# SCH.net
KiCad netlist of a schematic drawn in Altium Designer
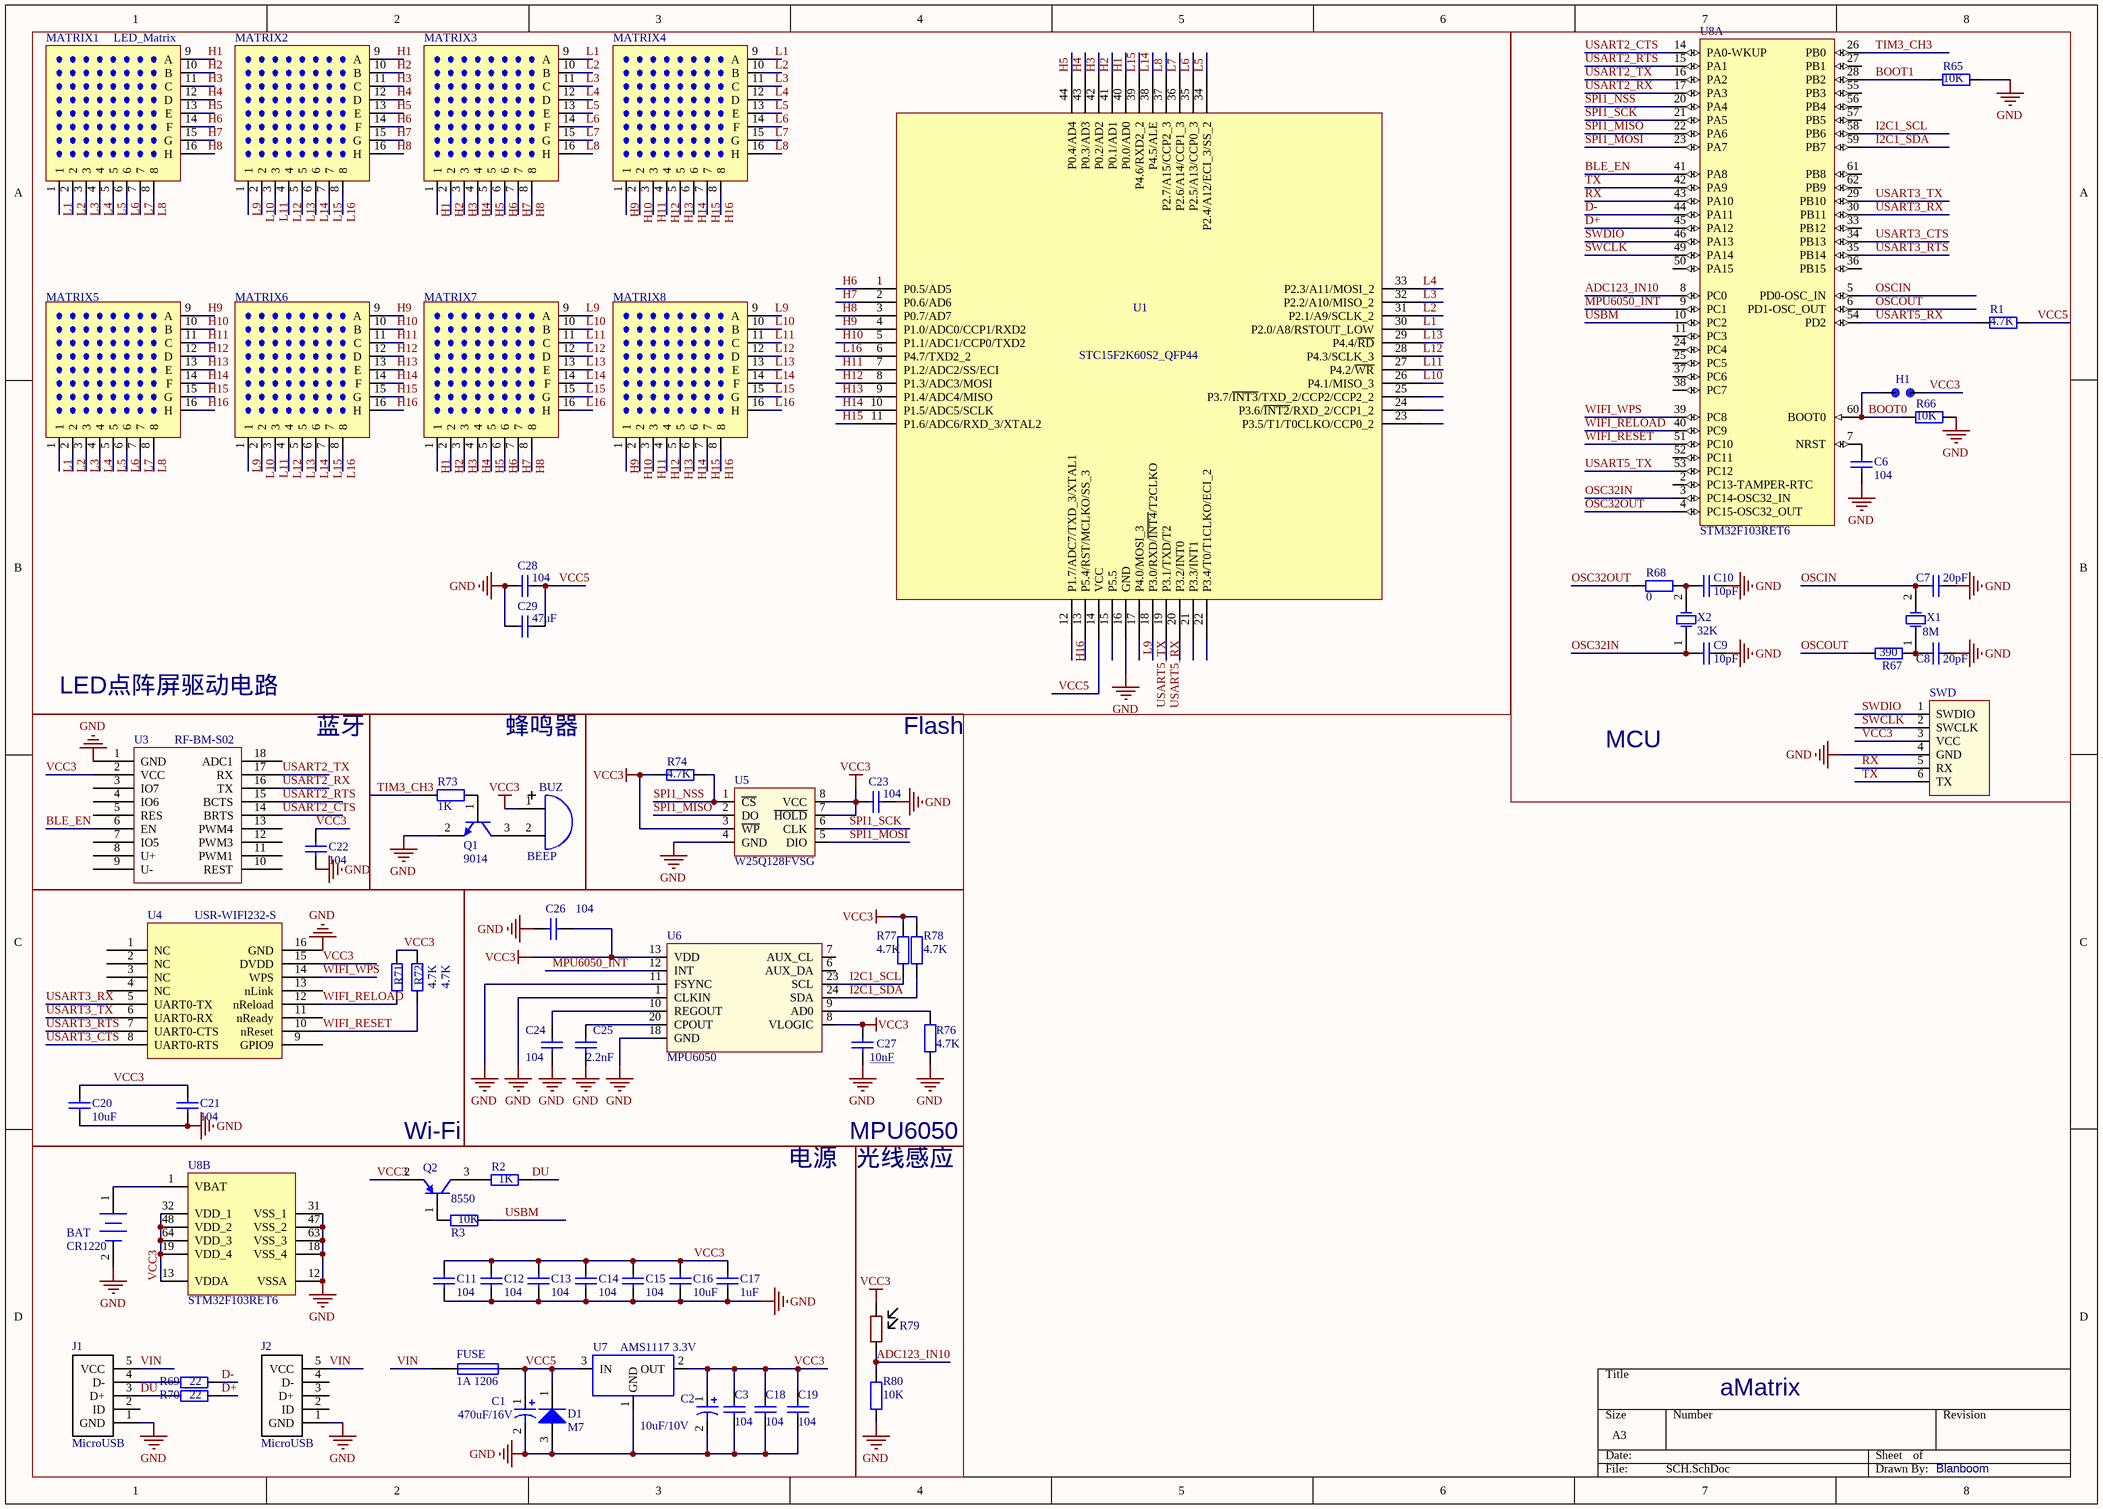
[diagram p0: SCH.SchDoc]

(export (version "E")
  (design (tool "Eeschema 10.0.6"))
  (components
    (comp (ref "BAT")
      (value "CR1220")
      (footprint "CR1220")
      (description "Multicell Battery")
      (libsource (lib "Miscellaneous Devices") (part "Battery"))
    )
    (comp (ref "BUZ") (value "BEEP") (footprint "BEEP") (libsource (lib "MyLib") (part "BEEP")))
    (comp (ref "C1")
      (value "470uF/16V")
      (footprint "7343")
      (description "Polarized Capacitor (Radial)")
      (fields (field (name "Comment") "Cap Pol1"))
      (libsource (lib "Miscellaneous Devices") (part "Cap Pol1"))
    )
    (comp (ref "C2")
      (value "10uF/10V")
      (footprint "1206_Diode")
      (description "Polarized Capacitor (Radial)")
      (fields (field (name "Comment") "Cap Pol1"))
      (libsource (lib "Miscellaneous Devices") (part "Cap Pol1"))
    )
    (comp (ref "C3")
      (value "104")
      (footprint "0805")
      (description "Capacitor")
      (fields (field (name "Comment") "Cap"))
      (libsource (lib "Miscellaneous Devices") (part "Cap"))
    )
    (comp (ref "C6")
      (value "104")
      (footprint "0805")
      (description "Capacitor")
      (libsource (lib "Miscellaneous Devices") (part "Cap"))
    )
    (comp (ref "C7")
      (value "20pF")
      (footprint "0805")
      (description "Capacitor")
      (fields (field (name "Comment") "Cap"))
      (libsource (lib "Miscellaneous Devices") (part "Cap"))
    )
    (comp (ref "C8")
      (value "20pF")
      (footprint "0805")
      (description "Capacitor")
      (fields (field (name "Comment") "Cap"))
      (libsource (lib "Miscellaneous Devices") (part "Cap"))
    )
    (comp (ref "C9")
      (value "10pF")
      (footprint "0805")
      (description "Capacitor")
      (fields (field (name "Comment") "Cap"))
      (libsource (lib "Miscellaneous Devices") (part "Cap"))
    )
    (comp (ref "C10")
      (value "10pF")
      (footprint "0805")
      (description "Capacitor")
      (fields (field (name "Comment") "Cap"))
      (libsource (lib "Miscellaneous Devices") (part "Cap"))
    )
    (comp (ref "C11")
      (value "104")
      (footprint "0805")
      (description "Capacitor")
      (fields (field (name "Comment") "Cap"))
      (libsource (lib "Miscellaneous Devices") (part "Cap"))
    )
    (comp (ref "C12")
      (value "104")
      (footprint "0805")
      (description "Capacitor")
      (fields (field (name "Comment") "Cap"))
      (libsource (lib "Miscellaneous Devices") (part "Cap"))
    )
    (comp (ref "C13")
      (value "104")
      (footprint "0805")
      (description "Capacitor")
      (fields (field (name "Comment") "Cap"))
      (libsource (lib "Miscellaneous Devices") (part "Cap"))
    )
    (comp (ref "C14")
      (value "104")
      (footprint "0805")
      (description "Capacitor")
      (fields (field (name "Comment") "Cap"))
      (libsource (lib "Miscellaneous Devices") (part "Cap"))
    )
    (comp (ref "C15")
      (value "104")
      (footprint "0805")
      (description "Capacitor")
      (fields (field (name "Comment") "Cap"))
      (libsource (lib "Miscellaneous Devices") (part "Cap"))
    )
    (comp (ref "C16")
      (value "10uF")
      (footprint "0805")
      (description "Capacitor")
      (fields (field (name "Comment") "Cap"))
      (libsource (lib "Miscellaneous Devices") (part "Cap"))
    )
    (comp (ref "C17")
      (value "1uF")
      (footprint "0805")
      (description "Capacitor")
      (fields (field (name "Comment") "Cap"))
      (libsource (lib "Miscellaneous Devices") (part "Cap"))
    )
    (comp (ref "C18")
      (value "104")
      (footprint "0805")
      (description "Capacitor")
      (fields (field (name "Comment") "Cap"))
      (libsource (lib "Miscellaneous Devices") (part "Cap"))
    )
    (comp (ref "C19")
      (value "104")
      (footprint "0805")
      (description "Capacitor")
      (fields (field (name "Comment") "Cap"))
      (libsource (lib "Miscellaneous Devices") (part "Cap"))
    )
    (comp (ref "C20")
      (value "10uF")
      (footprint "0805")
      (description "Capacitor")
      (fields (field (name "Comment") "Cap"))
      (libsource (lib "Miscellaneous Devices") (part "Cap"))
    )
    (comp (ref "C21")
      (value "104")
      (footprint "0805")
      (description "Capacitor")
      (fields (field (name "Comment") "Cap"))
      (libsource (lib "Miscellaneous Devices") (part "Cap"))
    )
    (comp (ref "C22")
      (value "104")
      (footprint "0805")
      (description "Capacitor")
      (fields (field (name "Comment") "Cap"))
      (libsource (lib "Miscellaneous Devices") (part "Cap"))
    )
    (comp (ref "C23")
      (value "104")
      (footprint "0805")
      (description "Capacitor")
      (fields (field (name "Comment") "Cap"))
      (libsource (lib "Miscellaneous Devices") (part "Cap"))
    )
    (comp (ref "C24")
      (value "104")
      (footprint "0805")
      (description "Capacitor")
      (fields (field (name "Comment") "Cap"))
      (libsource (lib "Miscellaneous Devices") (part "Cap"))
    )
    (comp (ref "C25")
      (value "2.2nF")
      (footprint "0805")
      (description "Capacitor")
      (fields (field (name "Comment") "Cap"))
      (libsource (lib "Miscellaneous Devices") (part "Cap"))
    )
    (comp (ref "C26")
      (value "104")
      (footprint "0805")
      (description "Capacitor")
      (fields (field (name "Comment") "Cap"))
      (libsource (lib "Miscellaneous Devices") (part "Cap"))
    )
    (comp (ref "C27")
      (value "10nF")
      (footprint "0805")
      (description "Capacitor")
      (fields (field (name "Comment") "Cap"))
      (libsource (lib "Miscellaneous Devices") (part "Cap"))
    )
    (comp (ref "C28")
      (value "104")
      (footprint "0805")
      (description "Capacitor")
      (fields (field (name "Comment") "Cap"))
      (libsource (lib "Miscellaneous Devices") (part "Cap"))
    )
    (comp (ref "C29")
      (value "47uF")
      (footprint "0805")
      (description "Capacitor")
      (fields (field (name "Comment") "Cap"))
      (libsource (lib "Miscellaneous Devices") (part "Cap"))
    )
    (comp (ref "D1")
      (value "M7")
      (footprint "DO-214AC")
      (description "Default Diode")
      (libsource (lib "Miscellaneous Devices") (part "Diode"))
    )
    (comp (ref "FUSE")
      (value "1A 1206")
      (footprint "1206")
      (description "Fuse")
      (libsource (lib "Miscellaneous Devices") (part "Fuse 1"))
    )
    (comp (ref "H1") (value "Header2") (footprint "Header2") (libsource (lib "SCH_Library") (part "Header2")))
    (comp (ref "J1")
      (value "MicroUSB")
      (footprint "MicroUSB")
      (description "Imported")
      (libsource (lib "SCH_Library") (part "MicroUSB"))
    )
    (comp (ref "J2")
      (value "MicroUSB")
      (footprint "MicroUSB")
      (description "Imported")
      (libsource (lib "SCH_Library") (part "MicroUSB"))
    )
    (comp (ref "MATRIX1")
      (value "LED_Matrix")
      (footprint "LED_Matrix")
      (libsource (lib "SCH_Library") (part "LED_Matrix"))
    )
    (comp (ref "MATRIX2")
      (value "LED_Matrix")
      (footprint "LED_Matrix")
      (libsource (lib "SCH_Library") (part "LED_Matrix"))
    )
    (comp (ref "MATRIX3")
      (value "LED_Matrix")
      (footprint "LED_Matrix")
      (libsource (lib "SCH_Library") (part "LED_Matrix"))
    )
    (comp (ref "MATRIX4")
      (value "LED_Matrix")
      (footprint "LED_Matrix")
      (libsource (lib "SCH_Library") (part "LED_Matrix"))
    )
    (comp (ref "MATRIX5")
      (value "LED_Matrix")
      (footprint "LED_Matrix")
      (libsource (lib "SCH_Library") (part "LED_Matrix"))
    )
    (comp (ref "MATRIX6")
      (value "LED_Matrix")
      (footprint "LED_Matrix")
      (libsource (lib "SCH_Library") (part "LED_Matrix"))
    )
    (comp (ref "MATRIX7")
      (value "LED_Matrix")
      (footprint "LED_Matrix")
      (libsource (lib "SCH_Library") (part "LED_Matrix"))
    )
    (comp (ref "MATRIX8")
      (value "LED_Matrix")
      (footprint "LED_Matrix")
      (libsource (lib "SCH_Library") (part "LED_Matrix"))
    )
    (comp (ref "Q1")
      (value "9014")
      (footprint "SOT-23-BJT")
      (description "NPN General Purpose Amplifier")
      (libsource (lib "Miscellaneous Devices") (part "2N3904"))
    )
    (comp (ref "Q2")
      (value "8550")
      (footprint "SOT-23-BJT")
      (description "PNP General Purpose Amplifier")
      (libsource (lib "Miscellaneous Devices") (part "2N3906"))
    )
    (comp (ref "R1")
      (value "4.7K")
      (footprint "0805")
      (description "Resistor")
      (libsource (lib "Miscellaneous Devices") (part "Res2"))
    )
    (comp (ref "R2")
      (value "1K")
      (footprint "0805")
      (description "Resistor")
      (libsource (lib "Miscellaneous Devices") (part "Res2"))
    )
    (comp (ref "R3")
      (value "10K")
      (footprint "0805")
      (description "Resistor")
      (libsource (lib "Miscellaneous Devices") (part "Res2"))
    )
    (comp (ref "R65")
      (value "10K")
      (footprint "0805")
      (description "Resistor")
      (fields (field (name "Comment") "Res2"))
      (libsource (lib "Miscellaneous Devices") (part "Res2"))
    )
    (comp (ref "R66")
      (value "10K")
      (footprint "0805")
      (description "Resistor")
      (libsource (lib "Miscellaneous Devices") (part "Res2"))
    )
    (comp (ref "R67")
      (value "390")
      (footprint "0805")
      (description "Resistor")
      (fields (field (name "Comment") "Res2"))
      (libsource (lib "Miscellaneous Devices") (part "Res2"))
    )
    (comp (ref "R68")
      (value "0")
      (footprint "0805")
      (description "Resistor")
      (fields (field (name "Comment") "Res2"))
      (libsource (lib "Miscellaneous Devices") (part "Res2"))
    )
    (comp (ref "R69")
      (value "22")
      (footprint "0805")
      (description "Resistor")
      (fields (field (name "Comment") "Res2"))
      (libsource (lib "Miscellaneous Devices") (part "Res2"))
    )
    (comp (ref "R70")
      (value "22")
      (footprint "0805")
      (description "Resistor")
      (fields (field (name "Comment") "Res2"))
      (libsource (lib "Miscellaneous Devices") (part "Res2"))
    )
    (comp (ref "R71")
      (value "4.7K")
      (footprint "0805")
      (description "Resistor")
      (fields (field (name "Comment") "Res2"))
      (libsource (lib "") (part "Res2_2"))
    )
    (comp (ref "R72")
      (value "4.7K")
      (footprint "0805")
      (description "Resistor")
      (fields (field (name "Comment") "Res2"))
      (libsource (lib "") (part "Res2_2"))
    )
    (comp (ref "R73")
      (value "1K")
      (footprint "0805")
      (description "Resistor")
      (fields (field (name "Comment") "Res2"))
      (libsource (lib "Miscellaneous Devices") (part "Res2"))
    )
    (comp (ref "R74")
      (value "4.7K")
      (footprint "0805")
      (description "Resistor")
      (fields (field (name "Comment") "Res2"))
      (libsource (lib "") (part "Res2_3"))
    )
    (comp (ref "R76")
      (value "4.7K")
      (footprint "0805")
      (description "Resistor")
      (fields (field (name "Comment") "Res2"))
      (libsource (lib "") (part "Res2_1"))
    )
    (comp (ref "R77")
      (value "4.7K")
      (footprint "0805")
      (description "Resistor")
      (fields (field (name "Comment") "Res2"))
      (libsource (lib "") (part "Res2_1"))
    )
    (comp (ref "R78")
      (value "4.7K")
      (footprint "0805")
      (description "Resistor")
      (fields (field (name "Comment") "Res2"))
      (libsource (lib "") (part "Res2_1"))
    )
    (comp (ref "R79") (value "Photoresistor") (libsource (lib "SCH_Library") (part "Photoresistor")))
    (comp (ref "R80")
      (value "10K")
      (footprint "0805")
      (description "Resistor")
      (fields (field (name "Comment") "Res2"))
      (libsource (lib "") (part "Res2_1"))
    )
    (comp (ref "SWD") (value "SWD") (footprint "HEADER6") (libsource (lib "SCH_Library") (part "SWD")))
    (comp (ref "U1")
      (value "STC15F2K60S2_QFP44")
      (footprint "LQFP44")
      (libsource (lib "SCH_Library") (part "STC15F2K60S2_QFP44"))
    )
    (comp (ref "U3")
      (value "RF-BM-S02")
      (footprint "RF-BM-S02")
      (libsource (lib "SCH_Library") (part "RF-BM-S02"))
    )
    (comp (ref "U4")
      (value "USR-WIFI232-S")
      (footprint "USR-WIFI232-S")
      (libsource (lib "SCH_Library") (part "USR-WIFI232-S"))
    )
    (comp (ref "U5")
      (value "W25Q128FVSG")
      (footprint "W25_Flash")
      (libsource (lib "SCH_Library") (part "W25Q128"))
    )
    (comp (ref "U6") (value "MPU6050") (footprint "MPU6050") (libsource (lib "SCH_Library") (part "MPU6050")))
    (comp (ref "U7")
      (value "AMS1117 3.3V")
      (footprint "SOT-223")
      (libsource (lib "SCH_Library") (part "AMS1117"))
    )
    (comp (ref "U8")
      (value "STM32F103RET6")
      (footprint "STM-LQFP64_M")
      (libsource (lib "SCH_Library") (part "STM32F103RET6"))
    )
    (comp (ref "X1")
      (value "8M")
      (footprint "XTAL_8M")
      (description "Crystal Oscillator")
      (libsource (lib "Miscellaneous Devices") (part "XTAL"))
    )
    (comp (ref "X2")
      (value "32K")
      (footprint "XTAL_32K")
      (description "Crystal Oscillator")
      (libsource (lib "Miscellaneous Devices") (part "XTAL"))
    )
  )
  (nets
    (net (code "1") (name "/ADC123_IN10") (class "Default")
      (node (ref "R79") (pin "2") (pinfunction "2_2") (pintype "passive"))
      (node (ref "R80") (pin "1") (pinfunction "1_1") (pintype "passive"))
      (node (ref "U8") (pin "8") (pinfunction "PC0_8") (pintype "bidirectional"))
    )
    (net (code "2") (name "/BLE_EN") (class "Default")
      (node (ref "U3") (pin "6") (pinfunction "EN_6") (pintype "passive"))
      (node (ref "U8") (pin "41") (pinfunction "PA8_41") (pintype "bidirectional"))
    )
    (net (code "3") (name "/BOOT0") (class "Default")
      (node (ref "H1") (pin "2") (pinfunction "2_2") (pintype "passive"))
      (node (ref "R66") (pin "1") (pinfunction "1_1") (pintype "passive"))
      (node (ref "U8") (pin "60") (pinfunction "BOOT0_60") (pintype "input"))
    )
    (net (code "4") (name "/BOOT1") (class "Default")
      (node (ref "R65") (pin "1") (pinfunction "1_1") (pintype "passive"))
      (node (ref "U8") (pin "28") (pinfunction "PB2_28") (pintype "bidirectional"))
    )
    (net (code "5") (name "/D+") (class "Default")
      (node (ref "R70") (pin "2") (pinfunction "2_2") (pintype "passive"))
      (node (ref "U8") (pin "45") (pinfunction "PA12_45") (pintype "bidirectional"))
    )
    (net (code "6") (name "/D-") (class "Default")
      (node (ref "R69") (pin "2") (pinfunction "2_2") (pintype "passive"))
      (node (ref "U8") (pin "44") (pinfunction "PA11_44") (pintype "bidirectional"))
    )
    (net (code "7") (name "/DU") (class "Default")
      (node (ref "J1") (pin "3") (pinfunction "D+_3") (pintype "passive"))
      (node (ref "R2") (pin "2") (pinfunction "2_2") (pintype "passive"))
      (node (ref "R70") (pin "1") (pinfunction "1_1") (pintype "passive"))
    )
    (net (code "8") (name "/H1") (class "Default")
      (node (ref "MATRIX1") (pin "9") (pinfunction "A_9") (pintype "passive"))
      (node (ref "MATRIX2") (pin "9") (pinfunction "A_9") (pintype "passive"))
      (node (ref "MATRIX3") (pin "1") (pinfunction "1_1") (pintype "passive"))
      (node (ref "MATRIX7") (pin "1") (pinfunction "1_1") (pintype "passive"))
      (node (ref "U1") (pin "40") (pinfunction "P0.0/AD0_40") (pintype "passive"))
    )
    (net (code "9") (name "/H2") (class "Default")
      (node (ref "MATRIX1") (pin "10") (pinfunction "B_10") (pintype "passive"))
      (node (ref "MATRIX2") (pin "10") (pinfunction "B_10") (pintype "passive"))
      (node (ref "MATRIX3") (pin "2") (pinfunction "2_2") (pintype "passive"))
      (node (ref "MATRIX7") (pin "2") (pinfunction "2_2") (pintype "passive"))
      (node (ref "U1") (pin "41") (pinfunction "P0.1/AD1_41") (pintype "passive"))
    )
    (net (code "10") (name "/H3") (class "Default")
      (node (ref "MATRIX1") (pin "11") (pinfunction "C_11") (pintype "passive"))
      (node (ref "MATRIX2") (pin "11") (pinfunction "C_11") (pintype "passive"))
      (node (ref "MATRIX3") (pin "3") (pinfunction "3_3") (pintype "passive"))
      (node (ref "MATRIX7") (pin "3") (pinfunction "3_3") (pintype "passive"))
      (node (ref "U1") (pin "42") (pinfunction "P0.2/AD2_42") (pintype "passive"))
    )
    (net (code "11") (name "/H4") (class "Default")
      (node (ref "MATRIX1") (pin "12") (pinfunction "D_12") (pintype "passive"))
      (node (ref "MATRIX2") (pin "12") (pinfunction "D_12") (pintype "passive"))
      (node (ref "MATRIX3") (pin "4") (pinfunction "4_4") (pintype "passive"))
      (node (ref "MATRIX7") (pin "4") (pinfunction "4_4") (pintype "passive"))
      (node (ref "U1") (pin "43") (pinfunction "P0.3/AD3_43") (pintype "passive"))
    )
    (net (code "12") (name "/H5") (class "Default")
      (node (ref "MATRIX1") (pin "13") (pinfunction "E_13") (pintype "passive"))
      (node (ref "MATRIX2") (pin "13") (pinfunction "E_13") (pintype "passive"))
      (node (ref "MATRIX3") (pin "5") (pinfunction "5_5") (pintype "passive"))
      (node (ref "MATRIX7") (pin "5") (pinfunction "5_5") (pintype "passive"))
      (node (ref "U1") (pin "44") (pinfunction "P0.4/AD4_44") (pintype "passive"))
    )
    (net (code "13") (name "/H6") (class "Default")
      (node (ref "MATRIX1") (pin "14") (pinfunction "F_14") (pintype "passive"))
      (node (ref "MATRIX2") (pin "14") (pinfunction "F_14") (pintype "passive"))
      (node (ref "MATRIX3") (pin "6") (pinfunction "6_6") (pintype "passive"))
      (node (ref "MATRIX7") (pin "6") (pinfunction "6_6") (pintype "passive"))
      (node (ref "U1") (pin "1") (pinfunction "P0.5/AD5_1") (pintype "passive"))
    )
    (net (code "14") (name "/H7") (class "Default")
      (node (ref "MATRIX1") (pin "15") (pinfunction "G_15") (pintype "passive"))
      (node (ref "MATRIX2") (pin "15") (pinfunction "G_15") (pintype "passive"))
      (node (ref "MATRIX3") (pin "7") (pinfunction "7_7") (pintype "passive"))
      (node (ref "MATRIX7") (pin "7") (pinfunction "7_7") (pintype "passive"))
      (node (ref "U1") (pin "2") (pinfunction "P0.6/AD6_2") (pintype "passive"))
    )
    (net (code "15") (name "/H8") (class "Default")
      (node (ref "MATRIX1") (pin "16") (pinfunction "H_16") (pintype "passive"))
      (node (ref "MATRIX2") (pin "16") (pinfunction "H_16") (pintype "passive"))
      (node (ref "MATRIX3") (pin "8") (pinfunction "8_8") (pintype "passive"))
      (node (ref "MATRIX7") (pin "8") (pinfunction "8_8") (pintype "passive"))
      (node (ref "U1") (pin "3") (pinfunction "P0.7/AD7_3") (pintype "passive"))
    )
    (net (code "16") (name "/H9") (class "Default")
      (node (ref "MATRIX4") (pin "1") (pinfunction "1_1") (pintype "passive"))
      (node (ref "MATRIX5") (pin "9") (pinfunction "A_9") (pintype "passive"))
      (node (ref "MATRIX6") (pin "9") (pinfunction "A_9") (pintype "passive"))
      (node (ref "MATRIX8") (pin "1") (pinfunction "1_1") (pintype "passive"))
      (node (ref "U1") (pin "4") (pinfunction "P1.0/ADC0/CCP1/RXD2_4") (pintype "passive"))
    )
    (net (code "17") (name "/H10") (class "Default")
      (node (ref "MATRIX4") (pin "2") (pinfunction "2_2") (pintype "passive"))
      (node (ref "MATRIX5") (pin "10") (pinfunction "B_10") (pintype "passive"))
      (node (ref "MATRIX6") (pin "10") (pinfunction "B_10") (pintype "passive"))
      (node (ref "MATRIX8") (pin "2") (pinfunction "2_2") (pintype "passive"))
      (node (ref "U1") (pin "5") (pinfunction "P1.1/ADC1/CCP0/TXD2_5") (pintype "passive"))
    )
    (net (code "18") (name "/H11") (class "Default")
      (node (ref "MATRIX4") (pin "3") (pinfunction "3_3") (pintype "passive"))
      (node (ref "MATRIX5") (pin "11") (pinfunction "C_11") (pintype "passive"))
      (node (ref "MATRIX6") (pin "11") (pinfunction "C_11") (pintype "passive"))
      (node (ref "MATRIX8") (pin "3") (pinfunction "3_3") (pintype "passive"))
      (node (ref "U1") (pin "7") (pinfunction "P1.2/ADC2/SS/ECI_7") (pintype "passive"))
    )
    (net (code "19") (name "/H12") (class "Default")
      (node (ref "MATRIX4") (pin "4") (pinfunction "4_4") (pintype "passive"))
      (node (ref "MATRIX5") (pin "12") (pinfunction "D_12") (pintype "passive"))
      (node (ref "MATRIX6") (pin "12") (pinfunction "D_12") (pintype "passive"))
      (node (ref "MATRIX8") (pin "4") (pinfunction "4_4") (pintype "passive"))
      (node (ref "U1") (pin "8") (pinfunction "P1.3/ADC3/MOSI_8") (pintype "passive"))
    )
    (net (code "20") (name "/H13") (class "Default")
      (node (ref "MATRIX4") (pin "5") (pinfunction "5_5") (pintype "passive"))
      (node (ref "MATRIX5") (pin "13") (pinfunction "E_13") (pintype "passive"))
      (node (ref "MATRIX6") (pin "13") (pinfunction "E_13") (pintype "passive"))
      (node (ref "MATRIX8") (pin "5") (pinfunction "5_5") (pintype "passive"))
      (node (ref "U1") (pin "9") (pinfunction "P1.4/ADC4/MISO_9") (pintype "passive"))
    )
    (net (code "21") (name "/H14") (class "Default")
      (node (ref "MATRIX4") (pin "6") (pinfunction "6_6") (pintype "passive"))
      (node (ref "MATRIX5") (pin "14") (pinfunction "F_14") (pintype "passive"))
      (node (ref "MATRIX6") (pin "14") (pinfunction "F_14") (pintype "passive"))
      (node (ref "MATRIX8") (pin "6") (pinfunction "6_6") (pintype "passive"))
      (node (ref "U1") (pin "10") (pinfunction "P1.5/ADC5/SCLK_10") (pintype "passive"))
    )
    (net (code "22") (name "/H15") (class "Default")
      (node (ref "MATRIX4") (pin "7") (pinfunction "7_7") (pintype "passive"))
      (node (ref "MATRIX5") (pin "15") (pinfunction "G_15") (pintype "passive"))
      (node (ref "MATRIX6") (pin "15") (pinfunction "G_15") (pintype "passive"))
      (node (ref "MATRIX8") (pin "7") (pinfunction "7_7") (pintype "passive"))
      (node (ref "U1") (pin "11") (pinfunction "P1.6/ADC6/RXD_3/XTAL2_11") (pintype "passive"))
    )
    (net (code "23") (name "/H16") (class "Default")
      (node (ref "MATRIX4") (pin "8") (pinfunction "8_8") (pintype "passive"))
      (node (ref "MATRIX5") (pin "16") (pinfunction "H_16") (pintype "passive"))
      (node (ref "MATRIX6") (pin "16") (pinfunction "H_16") (pintype "passive"))
      (node (ref "MATRIX8") (pin "8") (pinfunction "8_8") (pintype "passive"))
      (node (ref "U1") (pin "12") (pinfunction "P1.7/ADC7/TXD_3/XTAL1_12") (pintype "passive"))
    )
    (net (code "24") (name "/I2C1_SCL") (class "Default")
      (node (ref "R77") (pin "2") (pinfunction "2_2") (pintype "passive"))
      (node (ref "U6") (pin "23") (pinfunction "SCL_23") (pintype "passive"))
      (node (ref "U8") (pin "58") (pinfunction "PB6_58") (pintype "bidirectional"))
    )
    (net (code "25") (name "/I2C1_SDA") (class "Default")
      (node (ref "R78") (pin "2") (pinfunction "2_2") (pintype "passive"))
      (node (ref "U6") (pin "24") (pinfunction "SDA_24") (pintype "passive"))
      (node (ref "U8") (pin "59") (pinfunction "PB7_59") (pintype "bidirectional"))
    )
    (net (code "26") (name "/L1") (class "Default")
      (node (ref "MATRIX1") (pin "1") (pinfunction "1_1") (pintype "passive"))
      (node (ref "MATRIX3") (pin "9") (pinfunction "A_9") (pintype "passive"))
      (node (ref "MATRIX4") (pin "9") (pinfunction "A_9") (pintype "passive"))
      (node (ref "MATRIX5") (pin "1") (pinfunction "1_1") (pintype "passive"))
      (node (ref "U1") (pin "30") (pinfunction "P2.0/A8/RSTOUT_LOW_30") (pintype "passive"))
    )
    (net (code "27") (name "/L2") (class "Default")
      (node (ref "MATRIX1") (pin "2") (pinfunction "2_2") (pintype "passive"))
      (node (ref "MATRIX3") (pin "10") (pinfunction "B_10") (pintype "passive"))
      (node (ref "MATRIX4") (pin "10") (pinfunction "B_10") (pintype "passive"))
      (node (ref "MATRIX5") (pin "2") (pinfunction "2_2") (pintype "passive"))
      (node (ref "U1") (pin "31") (pinfunction "P2.1/A9/SCLK_2_31") (pintype "passive"))
    )
    (net (code "28") (name "/L3") (class "Default")
      (node (ref "MATRIX1") (pin "3") (pinfunction "3_3") (pintype "passive"))
      (node (ref "MATRIX3") (pin "11") (pinfunction "C_11") (pintype "passive"))
      (node (ref "MATRIX4") (pin "11") (pinfunction "C_11") (pintype "passive"))
      (node (ref "MATRIX5") (pin "3") (pinfunction "3_3") (pintype "passive"))
      (node (ref "U1") (pin "32") (pinfunction "P2.2/A10/MISO_2_32") (pintype "passive"))
    )
    (net (code "29") (name "/L4") (class "Default")
      (node (ref "MATRIX1") (pin "4") (pinfunction "4_4") (pintype "passive"))
      (node (ref "MATRIX3") (pin "12") (pinfunction "D_12") (pintype "passive"))
      (node (ref "MATRIX4") (pin "12") (pinfunction "D_12") (pintype "passive"))
      (node (ref "MATRIX5") (pin "4") (pinfunction "4_4") (pintype "passive"))
      (node (ref "U1") (pin "33") (pinfunction "P2.3/A11/MOSI_2_33") (pintype "passive"))
    )
    (net (code "30") (name "/L5") (class "Default")
      (node (ref "MATRIX1") (pin "5") (pinfunction "5_5") (pintype "passive"))
      (node (ref "MATRIX3") (pin "13") (pinfunction "E_13") (pintype "passive"))
      (node (ref "MATRIX4") (pin "13") (pinfunction "E_13") (pintype "passive"))
      (node (ref "MATRIX5") (pin "5") (pinfunction "5_5") (pintype "passive"))
      (node (ref "U1") (pin "34") (pinfunction "P2.4/A12/ECI_3/SS_2_34") (pintype "passive"))
    )
    (net (code "31") (name "/L6") (class "Default")
      (node (ref "MATRIX1") (pin "6") (pinfunction "6_6") (pintype "passive"))
      (node (ref "MATRIX3") (pin "14") (pinfunction "F_14") (pintype "passive"))
      (node (ref "MATRIX4") (pin "14") (pinfunction "F_14") (pintype "passive"))
      (node (ref "MATRIX5") (pin "6") (pinfunction "6_6") (pintype "passive"))
      (node (ref "U1") (pin "35") (pinfunction "P2.5/A13/CCP0_3_35") (pintype "passive"))
    )
    (net (code "32") (name "/L7") (class "Default")
      (node (ref "MATRIX1") (pin "7") (pinfunction "7_7") (pintype "passive"))
      (node (ref "MATRIX3") (pin "15") (pinfunction "G_15") (pintype "passive"))
      (node (ref "MATRIX4") (pin "15") (pinfunction "G_15") (pintype "passive"))
      (node (ref "MATRIX5") (pin "7") (pinfunction "7_7") (pintype "passive"))
      (node (ref "U1") (pin "36") (pinfunction "P2.6/A14/CCP1_3_36") (pintype "passive"))
    )
    (net (code "33") (name "/L8") (class "Default")
      (node (ref "MATRIX1") (pin "8") (pinfunction "8_8") (pintype "passive"))
      (node (ref "MATRIX3") (pin "16") (pinfunction "H_16") (pintype "passive"))
      (node (ref "MATRIX4") (pin "16") (pinfunction "H_16") (pintype "passive"))
      (node (ref "MATRIX5") (pin "8") (pinfunction "8_8") (pintype "passive"))
      (node (ref "U1") (pin "37") (pinfunction "P2.7/A15/CCP2_3_37") (pintype "passive"))
    )
    (net (code "34") (name "/L9") (class "Default")
      (node (ref "MATRIX2") (pin "1") (pinfunction "1_1") (pintype "passive"))
      (node (ref "MATRIX6") (pin "1") (pinfunction "1_1") (pintype "passive"))
      (node (ref "MATRIX7") (pin "9") (pinfunction "A_9") (pintype "passive"))
      (node (ref "MATRIX8") (pin "9") (pinfunction "A_9") (pintype "passive"))
      (node (ref "U1") (pin "17") (pinfunction "P4.0/MOSI_3_17") (pintype "passive"))
    )
    (net (code "35") (name "/L10") (class "Default")
      (node (ref "MATRIX2") (pin "2") (pinfunction "2_2") (pintype "passive"))
      (node (ref "MATRIX6") (pin "2") (pinfunction "2_2") (pintype "passive"))
      (node (ref "MATRIX7") (pin "10") (pinfunction "B_10") (pintype "passive"))
      (node (ref "MATRIX8") (pin "10") (pinfunction "B_10") (pintype "passive"))
      (node (ref "U1") (pin "26") (pinfunction "P4.1/MISO_3_26") (pintype "passive"))
    )
    (net (code "36") (name "/L11") (class "Default")
      (node (ref "MATRIX2") (pin "3") (pinfunction "3_3") (pintype "passive"))
      (node (ref "MATRIX6") (pin "3") (pinfunction "3_3") (pintype "passive"))
      (node (ref "MATRIX7") (pin "11") (pinfunction "C_11") (pintype "passive"))
      (node (ref "MATRIX8") (pin "11") (pinfunction "C_11") (pintype "passive"))
      (node (ref "U1") (pin "27") (pinfunction "P4.2/~{WR}_27") (pintype "passive"))
    )
    (net (code "37") (name "/L12") (class "Default")
      (node (ref "MATRIX2") (pin "4") (pinfunction "4_4") (pintype "passive"))
      (node (ref "MATRIX6") (pin "4") (pinfunction "4_4") (pintype "passive"))
      (node (ref "MATRIX7") (pin "12") (pinfunction "D_12") (pintype "passive"))
      (node (ref "MATRIX8") (pin "12") (pinfunction "D_12") (pintype "passive"))
      (node (ref "U1") (pin "28") (pinfunction "P4.3/SCLK_3_28") (pintype "passive"))
    )
    (net (code "38") (name "/L13") (class "Default")
      (node (ref "MATRIX2") (pin "5") (pinfunction "5_5") (pintype "passive"))
      (node (ref "MATRIX6") (pin "5") (pinfunction "5_5") (pintype "passive"))
      (node (ref "MATRIX7") (pin "13") (pinfunction "E_13") (pintype "passive"))
      (node (ref "MATRIX8") (pin "13") (pinfunction "E_13") (pintype "passive"))
      (node (ref "U1") (pin "29") (pinfunction "P4.4/~{RD}_29") (pintype "passive"))
    )
    (net (code "39") (name "/L14") (class "Default")
      (node (ref "MATRIX2") (pin "6") (pinfunction "6_6") (pintype "passive"))
      (node (ref "MATRIX6") (pin "6") (pinfunction "6_6") (pintype "passive"))
      (node (ref "MATRIX7") (pin "14") (pinfunction "F_14") (pintype "passive"))
      (node (ref "MATRIX8") (pin "14") (pinfunction "F_14") (pintype "passive"))
      (node (ref "U1") (pin "38") (pinfunction "P4.5/ALE_38") (pintype "passive"))
    )
    (net (code "40") (name "/L15") (class "Default")
      (node (ref "MATRIX2") (pin "7") (pinfunction "7_7") (pintype "passive"))
      (node (ref "MATRIX6") (pin "7") (pinfunction "7_7") (pintype "passive"))
      (node (ref "MATRIX7") (pin "15") (pinfunction "G_15") (pintype "passive"))
      (node (ref "MATRIX8") (pin "15") (pinfunction "G_15") (pintype "passive"))
      (node (ref "U1") (pin "39") (pinfunction "P4.6/RXD2_2_39") (pintype "passive"))
    )
    (net (code "41") (name "/L16") (class "Default")
      (node (ref "MATRIX2") (pin "8") (pinfunction "8_8") (pintype "passive"))
      (node (ref "MATRIX6") (pin "8") (pinfunction "8_8") (pintype "passive"))
      (node (ref "MATRIX7") (pin "16") (pinfunction "H_16") (pintype "passive"))
      (node (ref "MATRIX8") (pin "16") (pinfunction "H_16") (pintype "passive"))
      (node (ref "U1") (pin "6") (pinfunction "P4.7/TXD2_2_6") (pintype "passive"))
    )
    (net (code "42") (name "/MPU6050_INT") (class "Default")
      (node (ref "U6") (pin "12") (pinfunction "INT_12") (pintype "passive"))
      (node (ref "U8") (pin "9") (pinfunction "PC1_9") (pintype "bidirectional"))
    )
    (net (code "43") (name "/OSC32IN") (class "Default")
      (node (ref "C9") (pin "1") (pinfunction "1_1") (pintype "passive"))
      (node (ref "U8") (pin "3") (pinfunction "PC14-OSC32_IN_3") (pintype "bidirectional"))
      (node (ref "X2") (pin "1") (pinfunction "OSC1_1") (pintype "passive"))
    )
    (net (code "44") (name "/OSC32OUT") (class "Default")
      (node (ref "R68") (pin "1") (pinfunction "1_1") (pintype "passive"))
      (node (ref "U8") (pin "4") (pinfunction "PC15-OSC32_OUT_4") (pintype "bidirectional"))
    )
    (net (code "45") (name "/OSCIN") (class "Default")
      (node (ref "C7") (pin "1") (pinfunction "1_1") (pintype "passive"))
      (node (ref "U8") (pin "5") (pinfunction "PD0-OSC_IN_5") (pintype "bidirectional"))
      (node (ref "X1") (pin "2") (pinfunction "OSC2_2") (pintype "passive"))
    )
    (net (code "46") (name "/OSCOUT") (class "Default")
      (node (ref "R67") (pin "1") (pinfunction "1_1") (pintype "passive"))
      (node (ref "U8") (pin "6") (pinfunction "PD1-OSC_OUT_6") (pintype "bidirectional"))
    )
    (net (code "47") (name "/RX") (class "Default")
      (node (ref "SWD") (pin "5") (pinfunction "RX_5") (pintype "passive"))
      (node (ref "U8") (pin "43") (pinfunction "PA10_43") (pintype "bidirectional"))
    )
    (net (code "48") (name "/SPI1_MISO") (class "Default")
      (node (ref "U5") (pin "2") (pinfunction "DO_2") (pintype "passive"))
      (node (ref "U8") (pin "22") (pinfunction "PA6_22") (pintype "bidirectional"))
    )
    (net (code "49") (name "/SPI1_MOSI") (class "Default")
      (node (ref "U5") (pin "5") (pinfunction "DIO_5") (pintype "passive"))
      (node (ref "U8") (pin "23") (pinfunction "PA7_23") (pintype "bidirectional"))
    )
    (net (code "50") (name "/SPI1_NSS") (class "Default")
      (node (ref "R74") (pin "1") (pinfunction "1_1") (pintype "passive"))
      (node (ref "U5") (pin "1") (pinfunction "~{CS}_1") (pintype "passive"))
      (node (ref "U8") (pin "20") (pinfunction "PA4_20") (pintype "bidirectional"))
    )
    (net (code "51") (name "/SPI1_SCK") (class "Default")
      (node (ref "U5") (pin "6") (pinfunction "CLK_6") (pintype "passive"))
      (node (ref "U8") (pin "21") (pinfunction "PA5_21") (pintype "bidirectional"))
    )
    (net (code "52") (name "/SWCLK") (class "Default")
      (node (ref "SWD") (pin "2") (pinfunction "SWCLK_2") (pintype "passive"))
      (node (ref "U8") (pin "49") (pinfunction "PA14_49") (pintype "bidirectional"))
    )
    (net (code "53") (name "/SWDIO") (class "Default")
      (node (ref "SWD") (pin "1") (pinfunction "SWDIO_1") (pintype "passive"))
      (node (ref "U8") (pin "46") (pinfunction "PA13_46") (pintype "bidirectional"))
    )
    (net (code "54") (name "/TIM3_CH3") (class "Default")
      (node (ref "R73") (pin "1") (pinfunction "1_1") (pintype "passive"))
      (node (ref "U8") (pin "26") (pinfunction "PB0_26") (pintype "bidirectional"))
    )
    (net (code "55") (name "/TX") (class "Default")
      (node (ref "SWD") (pin "6") (pinfunction "TX_6") (pintype "passive"))
      (node (ref "U8") (pin "42") (pinfunction "PA9_42") (pintype "bidirectional"))
    )
    (net (code "56") (name "/USART2_CTS") (class "Default")
      (node (ref "U3") (pin "14") (pinfunction "BRTS_14") (pintype "passive"))
      (node (ref "U8") (pin "14") (pinfunction "PA0-WKUP_14") (pintype "bidirectional"))
    )
    (net (code "57") (name "/USART2_RTS") (class "Default")
      (node (ref "U3") (pin "15") (pinfunction "BCTS_15") (pintype "passive"))
      (node (ref "U8") (pin "15") (pinfunction "PA1_15") (pintype "bidirectional"))
    )
    (net (code "58") (name "/USART2_RX") (class "Default")
      (node (ref "U3") (pin "16") (pinfunction "TX_16") (pintype "passive"))
      (node (ref "U8") (pin "17") (pinfunction "PA3_17") (pintype "bidirectional"))
    )
    (net (code "59") (name "/USART2_TX") (class "Default")
      (node (ref "U3") (pin "17") (pinfunction "RX_17") (pintype "passive"))
      (node (ref "U8") (pin "16") (pinfunction "PA2_16") (pintype "bidirectional"))
    )
    (net (code "60") (name "/USART3_CTS") (class "Default")
      (node (ref "U4") (pin "8") (pinfunction "UART0-RTS_8") (pintype "passive"))
      (node (ref "U8") (pin "34") (pinfunction "PB13_34") (pintype "bidirectional"))
    )
    (net (code "61") (name "/USART3_RTS") (class "Default")
      (node (ref "U4") (pin "7") (pinfunction "UART0-CTS_7") (pintype "passive"))
      (node (ref "U8") (pin "35") (pinfunction "PB14_35") (pintype "bidirectional"))
    )
    (net (code "62") (name "/USART3_RX") (class "Default")
      (node (ref "U4") (pin "5") (pinfunction "UART0-TX_5") (pintype "passive"))
      (node (ref "U8") (pin "30") (pinfunction "PB11_30") (pintype "bidirectional"))
    )
    (net (code "63") (name "/USART3_TX") (class "Default")
      (node (ref "U4") (pin "6") (pinfunction "UART0-RX_6") (pintype "passive"))
      (node (ref "U8") (pin "29") (pinfunction "PB10_29") (pintype "bidirectional"))
    )
    (net (code "64") (name "/USART5_RX") (class "Default")
      (node (ref "R1") (pin "1") (pinfunction "1_1") (pintype "passive"))
      (node (ref "U1") (pin "19") (pinfunction "P3.1/TXD/T2_19") (pintype "passive"))
      (node (ref "U8") (pin "54") (pinfunction "PD2_54") (pintype "bidirectional"))
    )
    (net (code "65") (name "/USART5_TX") (class "Default")
      (node (ref "U1") (pin "18") (pinfunction "P3.0/RXD/~{INT4}/T2CLKO_18") (pintype "passive"))
      (node (ref "U8") (pin "53") (pinfunction "PC12_53") (pintype "bidirectional"))
    )
    (net (code "66") (name "/USBM") (class "Default")
      (node (ref "R3") (pin "2") (pinfunction "2_2") (pintype "passive"))
      (node (ref "U8") (pin "10") (pinfunction "PC2_10") (pintype "bidirectional"))
    )
    (net (code "67") (name "/VCC5") (class "Default")
      (node (ref "C1") (pin "1") (pinfunction "1_1") (pintype "passive"))
      (node (ref "C28") (pin "1") (pinfunction "1_1") (pintype "passive"))
      (node (ref "C29") (pin "1") (pinfunction "1_1") (pintype "passive"))
      (node (ref "D1") (pin "1") (pinfunction "K_1") (pintype "passive"))
      (node (ref "FUSE") (pin "2") (pinfunction "2_2") (pintype "passive"))
      (node (ref "R1") (pin "2") (pinfunction "2_2") (pintype "passive"))
      (node (ref "U1") (pin "14") (pinfunction "VCC_14") (pintype "passive"))
      (node (ref "U7") (pin "3") (pinfunction "IN_3") (pintype "passive"))
    )
    (net (code "68") (name "/VIN") (class "Default")
      (node (ref "FUSE") (pin "1") (pinfunction "1_1") (pintype "passive"))
      (node (ref "J1") (pin "5") (pinfunction "VCC_5") (pintype "passive"))
      (node (ref "J2") (pin "5") (pinfunction "VCC_5") (pintype "passive"))
    )
    (net (code "69") (name "/WIFI_RELOAD") (class "Default")
      (node (ref "R71") (pin "1") (pinfunction "1_1") (pintype "passive"))
      (node (ref "U4") (pin "12") (pinfunction "nReload_12") (pintype "passive"))
      (node (ref "U8") (pin "40") (pinfunction "PC9_40") (pintype "bidirectional"))
    )
    (net (code "70") (name "/WIFI_RESET") (class "Default")
      (node (ref "R72") (pin "1") (pinfunction "1_1") (pintype "passive"))
      (node (ref "U4") (pin "10") (pinfunction "nReset_10") (pintype "passive"))
      (node (ref "U8") (pin "51") (pinfunction "PC10_51") (pintype "bidirectional"))
    )
    (net (code "71") (name "/WIFI_WPS") (class "Default")
      (node (ref "U4") (pin "14") (pinfunction "WPS_14") (pintype "passive"))
      (node (ref "U8") (pin "39") (pinfunction "PC8_39") (pintype "bidirectional"))
    )
    (net (code "72") (name "GND") (class "Default")
      (node (ref "BAT") (pin "2") (pinfunction "-_2") (pintype "passive"))
      (node (ref "C1") (pin "2") (pinfunction "2_2") (pintype "passive"))
      (node (ref "C10") (pin "2") (pinfunction "2_2") (pintype "passive"))
      (node (ref "C11") (pin "1") (pinfunction "1_1") (pintype "passive"))
      (node (ref "C12") (pin "1") (pinfunction "1_1") (pintype "passive"))
      (node (ref "C13") (pin "1") (pinfunction "1_1") (pintype "passive"))
      (node (ref "C14") (pin "1") (pinfunction "1_1") (pintype "passive"))
      (node (ref "C15") (pin "1") (pinfunction "1_1") (pintype "passive"))
      (node (ref "C16") (pin "1") (pinfunction "1_1") (pintype "passive"))
      (node (ref "C17") (pin "1") (pinfunction "1_1") (pintype "passive"))
      (node (ref "C18") (pin "2") (pinfunction "2_2") (pintype "passive"))
      (node (ref "C19") (pin "2") (pinfunction "2_2") (pintype "passive"))
      (node (ref "C2") (pin "2") (pinfunction "2_2") (pintype "passive"))
      (node (ref "C20") (pin "1") (pinfunction "1_1") (pintype "passive"))
      (node (ref "C21") (pin "1") (pinfunction "1_1") (pintype "passive"))
      (node (ref "C22") (pin "1") (pinfunction "1_1") (pintype "passive"))
      (node (ref "C23") (pin "1") (pinfunction "1_1") (pintype "passive"))
      (node (ref "C24") (pin "2") (pinfunction "2_2") (pintype "passive"))
      (node (ref "C25") (pin "2") (pinfunction "2_2") (pintype "passive"))
      (node (ref "C26") (pin "2") (pinfunction "2_2") (pintype "passive"))
      (node (ref "C27") (pin "2") (pinfunction "2_2") (pintype "passive"))
      (node (ref "C28") (pin "2") (pinfunction "2_2") (pintype "passive"))
      (node (ref "C29") (pin "2") (pinfunction "2_2") (pintype "passive"))
      (node (ref "C3") (pin "2") (pinfunction "2_2") (pintype "passive"))
      (node (ref "C6") (pin "1") (pinfunction "1_1") (pintype "passive"))
      (node (ref "C7") (pin "2") (pinfunction "2_2") (pintype "passive"))
      (node (ref "C8") (pin "2") (pinfunction "2_2") (pintype "passive"))
      (node (ref "C9") (pin "2") (pinfunction "2_2") (pintype "passive"))
      (node (ref "D1") (pin "3") (pinfunction "A_3") (pintype "passive"))
      (node (ref "J1") (pin "1") (pinfunction "GND_1") (pintype "passive"))
      (node (ref "J2") (pin "1") (pinfunction "GND_1") (pintype "passive"))
      (node (ref "Q1") (pin "2") (pinfunction "E_2") (pintype "passive"))
      (node (ref "R65") (pin "2") (pinfunction "2_2") (pintype "passive"))
      (node (ref "R66") (pin "2") (pinfunction "2_2") (pintype "passive"))
      (node (ref "R76") (pin "2") (pinfunction "2_2") (pintype "passive"))
      (node (ref "R80") (pin "2") (pinfunction "2_2") (pintype "passive"))
      (node (ref "SWD") (pin "4") (pinfunction "GND_4") (pintype "passive"))
      (node (ref "U1") (pin "16") (pinfunction "GND_16") (pintype "passive"))
      (node (ref "U3") (pin "1") (pinfunction "GND_1") (pintype "passive"))
      (node (ref "U4") (pin "16") (pinfunction "GND_16") (pintype "passive"))
      (node (ref "U5") (pin "4") (pinfunction "GND_4") (pintype "passive"))
      (node (ref "U6") (pin "1") (pinfunction "CLKIN_1") (pintype "passive"))
      (node (ref "U6") (pin "11") (pinfunction "FSYNC_11") (pintype "passive"))
      (node (ref "U6") (pin "18") (pinfunction "GND_18") (pintype "passive"))
      (node (ref "U7") (pin "1") (pinfunction "GND_1") (pintype "passive"))
      (node (ref "U8") (pin "12") (pinfunction "VSSA_12") (pintype "power_in"))
      (node (ref "U8") (pin "18") (pinfunction "VSS_4_18") (pintype "power_in"))
      (node (ref "U8") (pin "31") (pinfunction "VSS_1_31") (pintype "power_in"))
      (node (ref "U8") (pin "47") (pinfunction "VSS_2_47") (pintype "power_in"))
      (node (ref "U8") (pin "63") (pinfunction "VSS_3_63") (pintype "power_in"))
    )
    (net (code "73") (name "Net-(BAT-+)") (class "Default")
      (node (ref "BAT") (pin "1") (pinfunction "+_1") (pintype "passive"))
      (node (ref "U8") (pin "1") (pinfunction "VBAT_1") (pintype "power_in"))
    )
    (net (code "74") (name "Net-(BUZ-B)") (class "Default")
      (node (ref "BUZ") (pin "2") (pinfunction "B_2") (pintype "passive"))
      (node (ref "Q1") (pin "3") (pinfunction "C_3") (pintype "passive"))
    )
    (net (code "75") (name "Net-(J1-D-)") (class "Default")
      (node (ref "J1") (pin "4") (pinfunction "D-_4") (pintype "passive"))
      (node (ref "R69") (pin "1") (pinfunction "1_1") (pintype "passive"))
    )
    (net (code "76") (name "Net-(Q1-B)") (class "Default")
      (node (ref "Q1") (pin "1") (pinfunction "B_1") (pintype "passive"))
      (node (ref "R73") (pin "2") (pinfunction "2_2") (pintype "passive"))
    )
    (net (code "77") (name "Net-(Q2-B)") (class "Default")
      (node (ref "Q2") (pin "1") (pinfunction "B_1") (pintype "passive"))
      (node (ref "R3") (pin "1") (pinfunction "1_1") (pintype "passive"))
    )
    (net (code "78") (name "Net-(Q2-C)") (class "Default")
      (node (ref "Q2") (pin "3") (pinfunction "C_3") (pintype "passive"))
      (node (ref "R2") (pin "1") (pinfunction "1_1") (pintype "passive"))
    )
    (net (code "79") (name "Net-(U6-AD0)") (class "Default")
      (node (ref "R76") (pin "1") (pinfunction "1_1") (pintype "passive"))
      (node (ref "U6") (pin "9") (pinfunction "AD0_9") (pintype "passive"))
    )
    (net (code "80") (name "Net-(U6-CPOUT)") (class "Default")
      (node (ref "C25") (pin "1") (pinfunction "1_1") (pintype "passive"))
      (node (ref "U6") (pin "20") (pinfunction "CPOUT_20") (pintype "passive"))
    )
    (net (code "81") (name "Net-(U6-REGOUT)") (class "Default")
      (node (ref "C24") (pin "1") (pinfunction "1_1") (pintype "passive"))
      (node (ref "U6") (pin "10") (pinfunction "REGOUT_10") (pintype "passive"))
    )
    (net (code "82") (name "Net-(U8A-NRST)") (class "Default")
      (node (ref "C6") (pin "2") (pinfunction "2_2") (pintype "passive"))
      (node (ref "U8") (pin "7") (pinfunction "NRST_7") (pintype "bidirectional"))
    )
    (net (code "83") (name "Net-(X1-OSC1)") (class "Default")
      (node (ref "C8") (pin "1") (pinfunction "1_1") (pintype "passive"))
      (node (ref "R67") (pin "2") (pinfunction "2_2") (pintype "passive"))
      (node (ref "X1") (pin "1") (pinfunction "OSC1_1") (pintype "passive"))
    )
    (net (code "84") (name "Net-(X2-OSC2)") (class "Default")
      (node (ref "C10") (pin "1") (pinfunction "1_1") (pintype "passive"))
      (node (ref "R68") (pin "2") (pinfunction "2_2") (pintype "passive"))
      (node (ref "X2") (pin "2") (pinfunction "OSC2_2") (pintype "passive"))
    )
    (net (code "85") (name "VCC3") (class "Default")
      (node (ref "BUZ") (pin "1") (pinfunction "A_1") (pintype "passive"))
      (node (ref "C11") (pin "2") (pinfunction "2_2") (pintype "passive"))
      (node (ref "C12") (pin "2") (pinfunction "2_2") (pintype "passive"))
      (node (ref "C13") (pin "2") (pinfunction "2_2") (pintype "passive"))
      (node (ref "C14") (pin "2") (pinfunction "2_2") (pintype "passive"))
      (node (ref "C15") (pin "2") (pinfunction "2_2") (pintype "passive"))
      (node (ref "C16") (pin "2") (pinfunction "2_2") (pintype "passive"))
      (node (ref "C17") (pin "2") (pinfunction "2_2") (pintype "passive"))
      (node (ref "C18") (pin "1") (pinfunction "1_1") (pintype "passive"))
      (node (ref "C19") (pin "1") (pinfunction "1_1") (pintype "passive"))
      (node (ref "C2") (pin "1") (pinfunction "1_1") (pintype "passive"))
      (node (ref "C20") (pin "2") (pinfunction "2_2") (pintype "passive"))
      (node (ref "C21") (pin "2") (pinfunction "2_2") (pintype "passive"))
      (node (ref "C22") (pin "2") (pinfunction "2_2") (pintype "passive"))
      (node (ref "C23") (pin "2") (pinfunction "2_2") (pintype "passive"))
      (node (ref "C26") (pin "1") (pinfunction "1_1") (pintype "passive"))
      (node (ref "C27") (pin "1") (pinfunction "1_1") (pintype "passive"))
      (node (ref "C3") (pin "1") (pinfunction "1_1") (pintype "passive"))
      (node (ref "H1") (pin "1") (pinfunction "1_1") (pintype "passive"))
      (node (ref "Q2") (pin "2") (pinfunction "E_2") (pintype "passive"))
      (node (ref "R71") (pin "2") (pinfunction "2_2") (pintype "passive"))
      (node (ref "R72") (pin "2") (pinfunction "2_2") (pintype "passive"))
      (node (ref "R74") (pin "2") (pinfunction "2_2") (pintype "passive"))
      (node (ref "R77") (pin "1") (pinfunction "1_1") (pintype "passive"))
      (node (ref "R78") (pin "1") (pinfunction "1_1") (pintype "passive"))
      (node (ref "R79") (pin "1") (pinfunction "1_1") (pintype "passive"))
      (node (ref "SWD") (pin "3") (pinfunction "VCC_3") (pintype "passive"))
      (node (ref "U3") (pin "2") (pinfunction "VCC_2") (pintype "passive"))
      (node (ref "U4") (pin "15") (pinfunction "DVDD_15") (pintype "passive"))
      (node (ref "U5") (pin "3") (pinfunction "~{WP}_3") (pintype "passive"))
      (node (ref "U5") (pin "7") (pinfunction "~{HOLD}_7") (pintype "passive"))
      (node (ref "U5") (pin "8") (pinfunction "VCC_8") (pintype "passive"))
      (node (ref "U6") (pin "13") (pinfunction "VDD_13") (pintype "passive"))
      (node (ref "U6") (pin "8") (pinfunction "VLOGIC_8") (pintype "passive"))
      (node (ref "U7") (pin "2") (pinfunction "OUT_2") (pintype "passive"))
      (node (ref "U8") (pin "13") (pinfunction "VDDA_13") (pintype "power_in"))
      (node (ref "U8") (pin "19") (pinfunction "VDD_4_19") (pintype "power_in"))
      (node (ref "U8") (pin "32") (pinfunction "VDD_1_32") (pintype "power_in"))
      (node (ref "U8") (pin "48") (pinfunction "VDD_2_48") (pintype "power_in"))
      (node (ref "U8") (pin "64") (pinfunction "VDD_3_64") (pintype "power_in"))
    )
    (net (code "86") (name "unconnected-(J1-ID-Pad2)") (class "Default")
      (node (ref "J1") (pin "2") (pinfunction "ID_2") (pintype "passive"))
    )
    (net (code "87") (name "unconnected-(J2-D+-Pad3)") (class "Default")
      (node (ref "J2") (pin "3") (pinfunction "D+_3") (pintype "passive"))
    )
    (net (code "88") (name "unconnected-(J2-D--Pad4)") (class "Default")
      (node (ref "J2") (pin "4") (pinfunction "D-_4") (pintype "passive"))
    )
    (net (code "89") (name "unconnected-(J2-ID-Pad2)") (class "Default")
      (node (ref "J2") (pin "2") (pinfunction "ID_2") (pintype "passive"))
    )
    (net (code "90") (name "unconnected-(U1-P3.2{slash}INT0-Pad20)") (class "Default")
      (node (ref "U1") (pin "20") (pinfunction "P3.2/INT0_20") (pintype "passive"))
    )
    (net (code "91") (name "unconnected-(U1-P3.3{slash}INT1-Pad21)") (class "Default")
      (node (ref "U1") (pin "21") (pinfunction "P3.3/INT1_21") (pintype "passive"))
    )
    (net (code "92") (name "unconnected-(U1-P3.4{slash}T0{slash}T1CLKO{slash}ECI_2-Pad22)") (class "Default")
      (node (ref "U1") (pin "22") (pinfunction "P3.4/T0/T1CLKO/ECI_2_22") (pintype "passive"))
    )
    (net (code "93") (name "unconnected-(U1-P3.5{slash}T1{slash}T0CLKO{slash}CCP0_2-Pad23)") (class "Default")
      (node (ref "U1") (pin "23") (pinfunction "P3.5/T1/T0CLKO/CCP0_2_23") (pintype "passive"))
    )
    (net (code "94") (name "unconnected-(U1-P3.6{slash}~{INT2}{slash}RXD_2{slash}CCP1_2-Pad24)") (class "Default")
      (node (ref "U1") (pin "24") (pinfunction "P3.6/~{INT2}/RXD_2/CCP1_2_24") (pintype "passive"))
    )
    (net (code "95") (name "unconnected-(U1-P3.7{slash}~{INT3}{slash}TXD_2{slash}CCP2{slash}CCP2_2-Pad25)") (class "Default")
      (node (ref "U1") (pin "25") (pinfunction "P3.7/~{INT3}/TXD_2/CCP2/CCP2_2_25") (pintype "passive"))
    )
    (net (code "96") (name "unconnected-(U1-P5.4{slash}RST{slash}MCLKO{slash}SS_3-Pad13)") (class "Default")
      (node (ref "U1") (pin "13") (pinfunction "P5.4/RST/MCLKO/SS_3_13") (pintype "passive"))
    )
    (net (code "97") (name "unconnected-(U1-P5.5-Pad15)") (class "Default")
      (node (ref "U1") (pin "15") (pinfunction "P5.5_15") (pintype "passive"))
    )
    (net (code "98") (name "unconnected-(U3-ADC1-Pad18)") (class "Default")
      (node (ref "U3") (pin "18") (pinfunction "ADC1_18") (pintype "passive"))
    )
    (net (code "99") (name "unconnected-(U3-IO5-Pad7)") (class "Default")
      (node (ref "U3") (pin "7") (pinfunction "IO5_7") (pintype "passive"))
    )
    (net (code "100") (name "unconnected-(U3-IO6-Pad4)") (class "Default")
      (node (ref "U3") (pin "4") (pinfunction "IO6_4") (pintype "passive"))
    )
    (net (code "101") (name "unconnected-(U3-IO7-Pad3)") (class "Default")
      (node (ref "U3") (pin "3") (pinfunction "IO7_3") (pintype "passive"))
    )
    (net (code "102") (name "unconnected-(U3-PWM1-Pad11)") (class "Default")
      (node (ref "U3") (pin "11") (pinfunction "PWM1_11") (pintype "passive"))
    )
    (net (code "103") (name "unconnected-(U3-PWM3-Pad12)") (class "Default")
      (node (ref "U3") (pin "12") (pinfunction "PWM3_12") (pintype "passive"))
    )
    (net (code "104") (name "unconnected-(U3-PWM4-Pad13)") (class "Default")
      (node (ref "U3") (pin "13") (pinfunction "PWM4_13") (pintype "passive"))
    )
    (net (code "105") (name "unconnected-(U3-RES-Pad5)") (class "Default")
      (node (ref "U3") (pin "5") (pinfunction "RES_5") (pintype "passive"))
    )
    (net (code "106") (name "unconnected-(U3-REST-Pad10)") (class "Default")
      (node (ref "U3") (pin "10") (pinfunction "REST_10") (pintype "passive"))
    )
    (net (code "107") (name "unconnected-(U3-U+-Pad8)") (class "Default")
      (node (ref "U3") (pin "8") (pinfunction "U+_8") (pintype "passive"))
    )
    (net (code "108") (name "unconnected-(U3-U--Pad9)") (class "Default")
      (node (ref "U3") (pin "9") (pinfunction "U-_9") (pintype "passive"))
    )
    (net (code "109") (name "unconnected-(U4-GPIO9-Pad9)") (class "Default")
      (node (ref "U4") (pin "9") (pinfunction "GPIO9_9") (pintype "passive"))
    )
    (net (code "110") (name "unconnected-(U4-NC-Pad1)") (class "Default")
      (node (ref "U4") (pin "1") (pinfunction "NC_1") (pintype "passive"))
    )
    (net (code "111") (name "unconnected-(U4-NC-Pad2)") (class "Default")
      (node (ref "U4") (pin "2") (pinfunction "NC_2") (pintype "passive"))
    )
    (net (code "112") (name "unconnected-(U4-NC-Pad3)") (class "Default")
      (node (ref "U4") (pin "3") (pinfunction "NC_3") (pintype "passive"))
    )
    (net (code "113") (name "unconnected-(U4-NC-Pad4)") (class "Default")
      (node (ref "U4") (pin "4") (pinfunction "NC_4") (pintype "passive"))
    )
    (net (code "114") (name "unconnected-(U4-nLink-Pad13)") (class "Default")
      (node (ref "U4") (pin "13") (pinfunction "nLink_13") (pintype "passive"))
    )
    (net (code "115") (name "unconnected-(U4-nReady-Pad11)") (class "Default")
      (node (ref "U4") (pin "11") (pinfunction "nReady_11") (pintype "passive"))
    )
    (net (code "116") (name "unconnected-(U6-AUX_CL-Pad7)") (class "Default")
      (node (ref "U6") (pin "7") (pinfunction "AUX_CL_7") (pintype "passive"))
    )
    (net (code "117") (name "unconnected-(U6-AUX_DA-Pad6)") (class "Default")
      (node (ref "U6") (pin "6") (pinfunction "AUX_DA_6") (pintype "passive"))
    )
    (net (code "118") (name "unconnected-(U8A-PA15-Pad50)") (class "Default")
      (node (ref "U8") (pin "50") (pinfunction "PA15_50") (pintype "bidirectional"))
    )
    (net (code "119") (name "unconnected-(U8A-PB1-Pad27)") (class "Default")
      (node (ref "U8") (pin "27") (pinfunction "PB1_27") (pintype "bidirectional"))
    )
    (net (code "120") (name "unconnected-(U8A-PB3-Pad55)") (class "Default")
      (node (ref "U8") (pin "55") (pinfunction "PB3_55") (pintype "bidirectional"))
    )
    (net (code "121") (name "unconnected-(U8A-PB4-Pad56)") (class "Default")
      (node (ref "U8") (pin "56") (pinfunction "PB4_56") (pintype "bidirectional"))
    )
    (net (code "122") (name "unconnected-(U8A-PB5-Pad57)") (class "Default")
      (node (ref "U8") (pin "57") (pinfunction "PB5_57") (pintype "bidirectional"))
    )
    (net (code "123") (name "unconnected-(U8A-PB8-Pad61)") (class "Default")
      (node (ref "U8") (pin "61") (pinfunction "PB8_61") (pintype "bidirectional"))
    )
    (net (code "124") (name "unconnected-(U8A-PB9-Pad62)") (class "Default")
      (node (ref "U8") (pin "62") (pinfunction "PB9_62") (pintype "bidirectional"))
    )
    (net (code "125") (name "unconnected-(U8A-PB12-Pad33)") (class "Default")
      (node (ref "U8") (pin "33") (pinfunction "PB12_33") (pintype "bidirectional"))
    )
    (net (code "126") (name "unconnected-(U8A-PB15-Pad36)") (class "Default")
      (node (ref "U8") (pin "36") (pinfunction "PB15_36") (pintype "bidirectional"))
    )
    (net (code "127") (name "unconnected-(U8A-PC3-Pad11)") (class "Default")
      (node (ref "U8") (pin "11") (pinfunction "PC3_11") (pintype "bidirectional"))
    )
    (net (code "128") (name "unconnected-(U8A-PC4-Pad24)") (class "Default")
      (node (ref "U8") (pin "24") (pinfunction "PC4_24") (pintype "bidirectional"))
    )
    (net (code "129") (name "unconnected-(U8A-PC5-Pad25)") (class "Default")
      (node (ref "U8") (pin "25") (pinfunction "PC5_25") (pintype "bidirectional"))
    )
    (net (code "130") (name "unconnected-(U8A-PC6-Pad37)") (class "Default")
      (node (ref "U8") (pin "37") (pinfunction "PC6_37") (pintype "bidirectional"))
    )
    (net (code "131") (name "unconnected-(U8A-PC7-Pad38)") (class "Default")
      (node (ref "U8") (pin "38") (pinfunction "PC7_38") (pintype "bidirectional"))
    )
    (net (code "132") (name "unconnected-(U8A-PC11-Pad52)") (class "Default")
      (node (ref "U8") (pin "52") (pinfunction "PC11_52") (pintype "bidirectional"))
    )
    (net (code "133") (name "unconnected-(U8A-PC13-TAMPER-RTC-Pad2)") (class "Default")
      (node (ref "U8") (pin "2") (pinfunction "PC13-TAMPER-RTC_2") (pintype "bidirectional"))
    )
  )
)
